# W061C.net
KiCad netlist of a schematic drawn in EAGLE
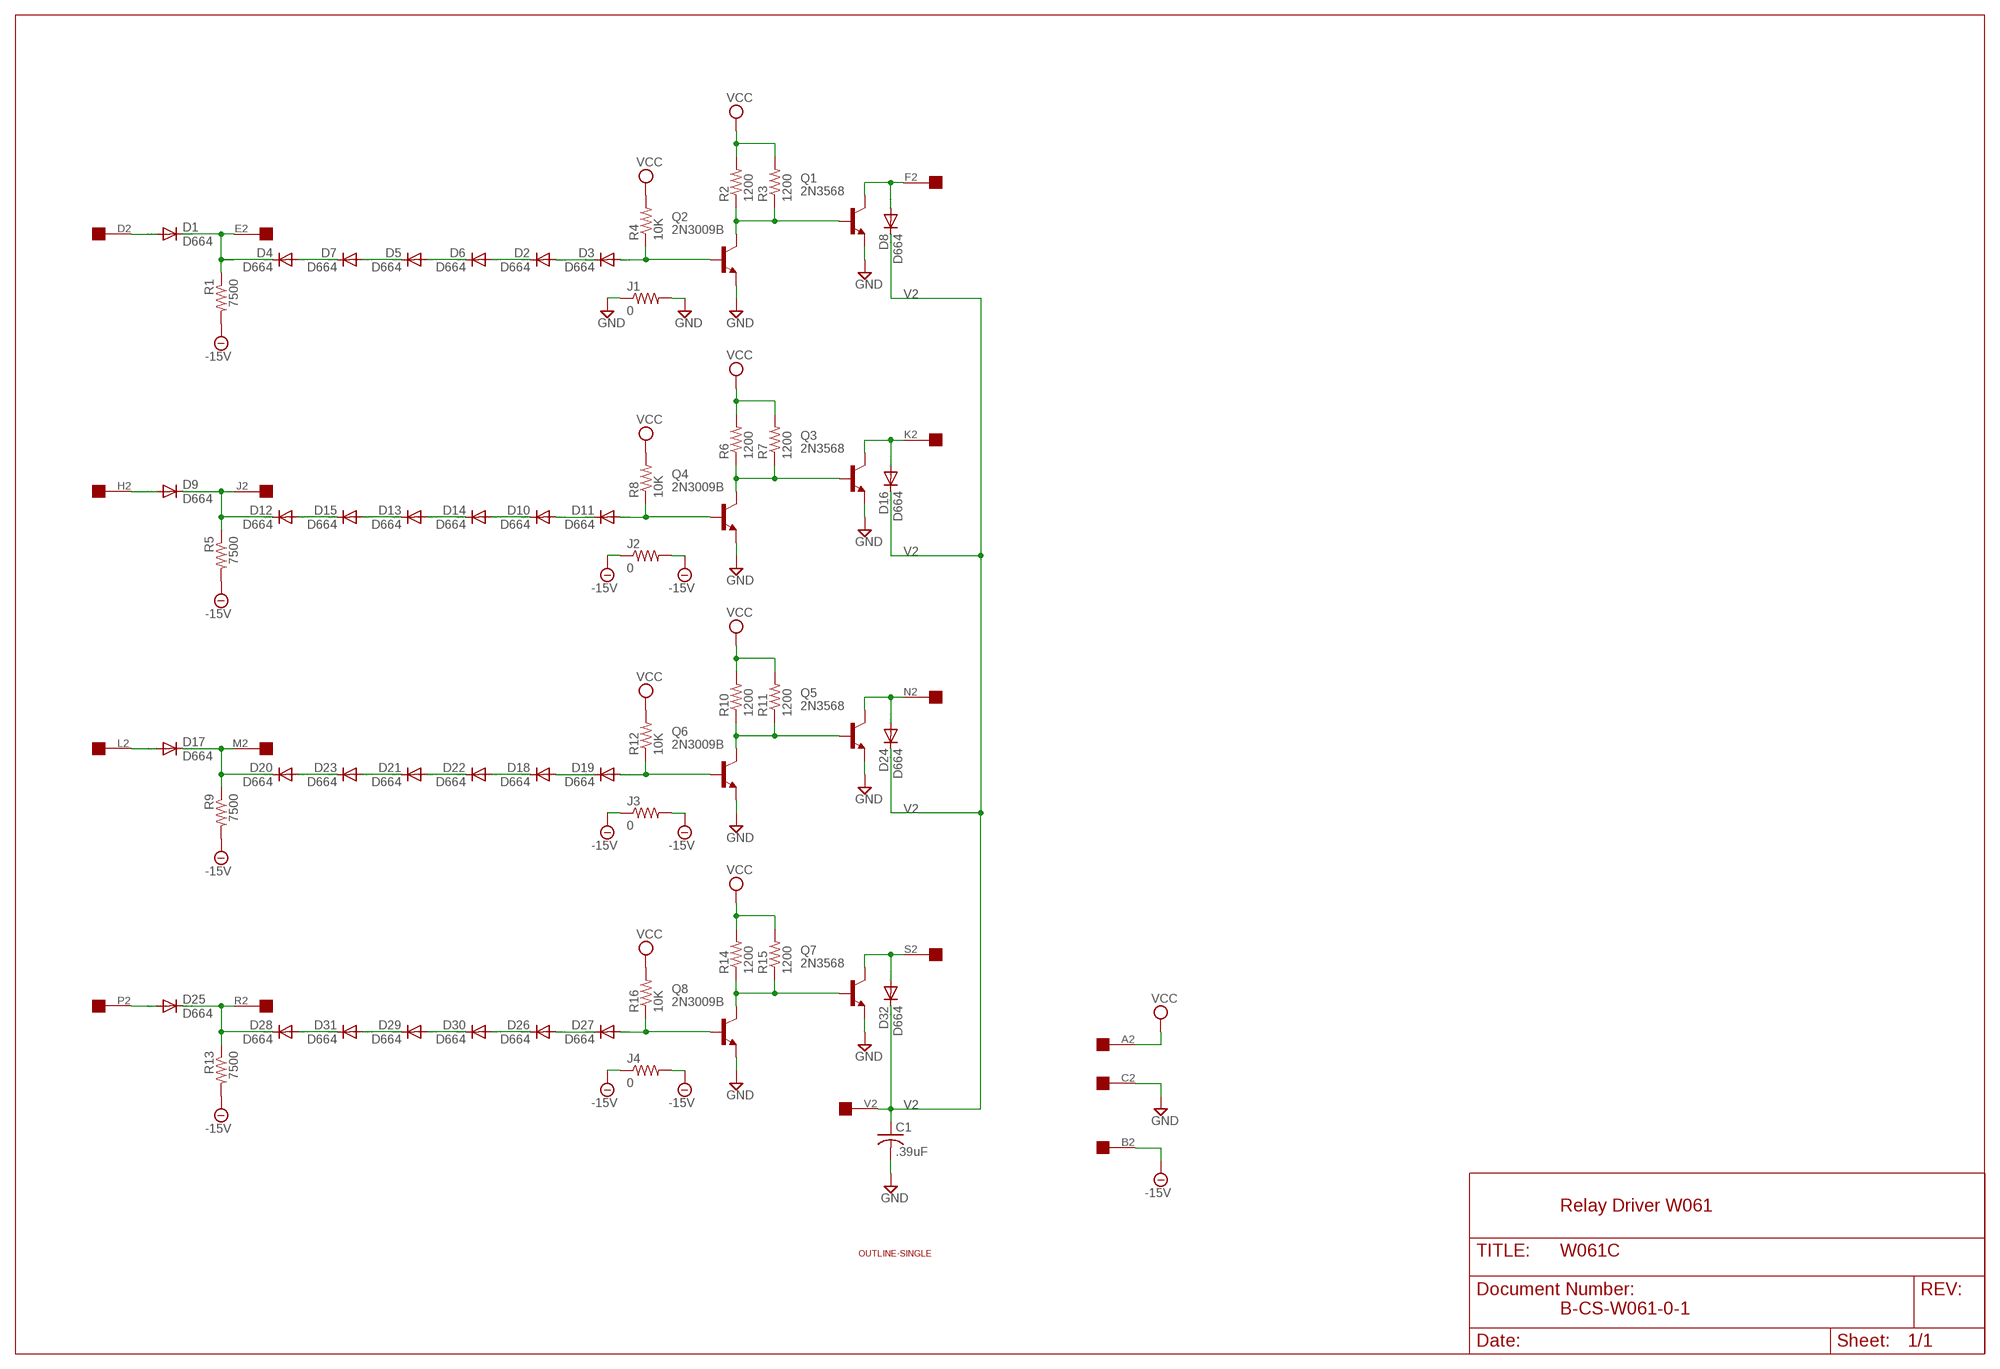
[diagram p0: schematic, sheet 1]

(export (version "E")
  (design (tool "Eeschema 10.0.6"))
  (components
    (comp (ref "C1")
      (value ".39uF")
      (footprint "eagle-import:C375-155X418")
      (libsource (lib "eagle-import") (part "C-US375-155X418"))
    )
    (comp (ref "D1")
      (value "D664")
      (footprint "eagle-import:DO35-10")
      (libsource (lib "eagle-import") (part "DIODE-DO35-10"))
    )
    (comp (ref "D2")
      (value "D664")
      (footprint "eagle-import:DO35-10")
      (libsource (lib "eagle-import") (part "DIODE-DO35-10"))
    )
    (comp (ref "D3")
      (value "D664")
      (footprint "eagle-import:DO35-10")
      (libsource (lib "eagle-import") (part "DIODE-DO35-10"))
    )
    (comp (ref "D4")
      (value "D664")
      (footprint "eagle-import:DO35-10")
      (libsource (lib "eagle-import") (part "DIODE-DO35-10"))
    )
    (comp (ref "D5")
      (value "D664")
      (footprint "eagle-import:DO35-10")
      (libsource (lib "eagle-import") (part "DIODE-DO35-10"))
    )
    (comp (ref "D6")
      (value "D664")
      (footprint "eagle-import:DO35-10")
      (libsource (lib "eagle-import") (part "DIODE-DO35-10"))
    )
    (comp (ref "D7")
      (value "D664")
      (footprint "eagle-import:DO35-10")
      (libsource (lib "eagle-import") (part "DIODE-DO35-10"))
    )
    (comp (ref "D8")
      (value "D664")
      (footprint "eagle-import:DO35-10")
      (libsource (lib "eagle-import") (part "DIODE-DO35-10"))
    )
    (comp (ref "D9")
      (value "D664")
      (footprint "eagle-import:DO35-10")
      (libsource (lib "eagle-import") (part "DIODE-DO35-10"))
    )
    (comp (ref "D10")
      (value "D664")
      (footprint "eagle-import:DO35-10")
      (libsource (lib "eagle-import") (part "DIODE-DO35-10"))
    )
    (comp (ref "D11")
      (value "D664")
      (footprint "eagle-import:DO35-10")
      (libsource (lib "eagle-import") (part "DIODE-DO35-10"))
    )
    (comp (ref "D12")
      (value "D664")
      (footprint "eagle-import:DO35-10")
      (libsource (lib "eagle-import") (part "DIODE-DO35-10"))
    )
    (comp (ref "D13")
      (value "D664")
      (footprint "eagle-import:DO35-10")
      (libsource (lib "eagle-import") (part "DIODE-DO35-10"))
    )
    (comp (ref "D14")
      (value "D664")
      (footprint "eagle-import:DO35-10")
      (libsource (lib "eagle-import") (part "DIODE-DO35-10"))
    )
    (comp (ref "D15")
      (value "D664")
      (footprint "eagle-import:DO35-10")
      (libsource (lib "eagle-import") (part "DIODE-DO35-10"))
    )
    (comp (ref "D16")
      (value "D664")
      (footprint "eagle-import:DO35-10")
      (libsource (lib "eagle-import") (part "DIODE-DO35-10"))
    )
    (comp (ref "D17")
      (value "D664")
      (footprint "eagle-import:DO35-10")
      (libsource (lib "eagle-import") (part "DIODE-DO35-10"))
    )
    (comp (ref "D18")
      (value "D664")
      (footprint "eagle-import:DO35-10")
      (libsource (lib "eagle-import") (part "DIODE-DO35-10"))
    )
    (comp (ref "D19")
      (value "D664")
      (footprint "eagle-import:DO35-10")
      (libsource (lib "eagle-import") (part "DIODE-DO35-10"))
    )
    (comp (ref "D20")
      (value "D664")
      (footprint "eagle-import:DO35-10")
      (libsource (lib "eagle-import") (part "DIODE-DO35-10"))
    )
    (comp (ref "D21")
      (value "D664")
      (footprint "eagle-import:DO35-10")
      (libsource (lib "eagle-import") (part "DIODE-DO35-10"))
    )
    (comp (ref "D22")
      (value "D664")
      (footprint "eagle-import:DO35-10")
      (libsource (lib "eagle-import") (part "DIODE-DO35-10"))
    )
    (comp (ref "D23")
      (value "D664")
      (footprint "eagle-import:DO35-10")
      (libsource (lib "eagle-import") (part "DIODE-DO35-10"))
    )
    (comp (ref "D24")
      (value "D664")
      (footprint "eagle-import:DO35-10")
      (libsource (lib "eagle-import") (part "DIODE-DO35-10"))
    )
    (comp (ref "D25")
      (value "D664")
      (footprint "eagle-import:DO35-10")
      (libsource (lib "eagle-import") (part "DIODE-DO35-10"))
    )
    (comp (ref "D26")
      (value "D664")
      (footprint "eagle-import:DO35-10")
      (libsource (lib "eagle-import") (part "DIODE-DO35-10"))
    )
    (comp (ref "D27")
      (value "D664")
      (footprint "eagle-import:DO35-10")
      (libsource (lib "eagle-import") (part "DIODE-DO35-10"))
    )
    (comp (ref "D28")
      (value "D664")
      (footprint "eagle-import:DO35-10")
      (libsource (lib "eagle-import") (part "DIODE-DO35-10"))
    )
    (comp (ref "D29")
      (value "D664")
      (footprint "eagle-import:DO35-10")
      (libsource (lib "eagle-import") (part "DIODE-DO35-10"))
    )
    (comp (ref "D30")
      (value "D664")
      (footprint "eagle-import:DO35-10")
      (libsource (lib "eagle-import") (part "DIODE-DO35-10"))
    )
    (comp (ref "D31")
      (value "D664")
      (footprint "eagle-import:DO35-10")
      (libsource (lib "eagle-import") (part "DIODE-DO35-10"))
    )
    (comp (ref "D32")
      (value "D664")
      (footprint "eagle-import:DO35-10")
      (libsource (lib "eagle-import") (part "DIODE-DO35-10"))
    )
    (comp (ref "J1")
      (value "0")
      (footprint "eagle-import:0207_10")
      (libsource (lib "eagle-import") (part "R-US_0207/10"))
    )
    (comp (ref "J2")
      (value "0")
      (footprint "eagle-import:0207_10")
      (libsource (lib "eagle-import") (part "R-US_0207/10"))
    )
    (comp (ref "J3")
      (value "0")
      (footprint "eagle-import:0207_10")
      (libsource (lib "eagle-import") (part "R-US_0207/10"))
    )
    (comp (ref "J4")
      (value "0")
      (footprint "eagle-import:0207_10")
      (libsource (lib "eagle-import") (part "R-US_0207/10"))
    )
    (comp (ref "Q1")
      (value "2N3568")
      (footprint "eagle-import:TO5")
      (libsource (lib "eagle-import") (part "-NPN-TO5"))
    )
    (comp (ref "Q2")
      (value "2N3009B")
      (footprint "eagle-import:TO5")
      (libsource (lib "eagle-import") (part "-NPN-TO5"))
    )
    (comp (ref "Q3")
      (value "2N3568")
      (footprint "eagle-import:TO5")
      (libsource (lib "eagle-import") (part "-NPN-TO5"))
    )
    (comp (ref "Q4")
      (value "2N3009B")
      (footprint "eagle-import:TO5")
      (libsource (lib "eagle-import") (part "-NPN-TO5"))
    )
    (comp (ref "Q5")
      (value "2N3568")
      (footprint "eagle-import:TO5")
      (libsource (lib "eagle-import") (part "-NPN-TO5"))
    )
    (comp (ref "Q6")
      (value "2N3009B")
      (footprint "eagle-import:TO5")
      (libsource (lib "eagle-import") (part "-NPN-TO5"))
    )
    (comp (ref "Q7")
      (value "2N3568")
      (footprint "eagle-import:TO5")
      (libsource (lib "eagle-import") (part "-NPN-TO5"))
    )
    (comp (ref "Q8")
      (value "2N3009B")
      (footprint "eagle-import:TO5")
      (libsource (lib "eagle-import") (part "-NPN-TO5"))
    )
    (comp (ref "R1")
      (value "7500")
      (footprint "eagle-import:0207_10")
      (libsource (lib "eagle-import") (part "R-US_0207/10"))
    )
    (comp (ref "R2")
      (value "1200")
      (footprint "eagle-import:0207_10")
      (libsource (lib "eagle-import") (part "R-US_0207/10"))
    )
    (comp (ref "R3")
      (value "1200")
      (footprint "eagle-import:0207_10")
      (libsource (lib "eagle-import") (part "R-US_0207/10"))
    )
    (comp (ref "R4")
      (value "10K")
      (footprint "eagle-import:0207_10")
      (libsource (lib "eagle-import") (part "R-US_0207/10"))
    )
    (comp (ref "R5")
      (value "7500")
      (footprint "eagle-import:0207_10")
      (libsource (lib "eagle-import") (part "R-US_0207/10"))
    )
    (comp (ref "R6")
      (value "1200")
      (footprint "eagle-import:0207_10")
      (libsource (lib "eagle-import") (part "R-US_0207/10"))
    )
    (comp (ref "R7")
      (value "1200")
      (footprint "eagle-import:0207_10")
      (libsource (lib "eagle-import") (part "R-US_0207/10"))
    )
    (comp (ref "R8")
      (value "10K")
      (footprint "eagle-import:0207_10")
      (libsource (lib "eagle-import") (part "R-US_0207/10"))
    )
    (comp (ref "R9")
      (value "7500")
      (footprint "eagle-import:0207_10")
      (libsource (lib "eagle-import") (part "R-US_0207/10"))
    )
    (comp (ref "R10")
      (value "1200")
      (footprint "eagle-import:0207_10")
      (libsource (lib "eagle-import") (part "R-US_0207/10"))
    )
    (comp (ref "R11")
      (value "1200")
      (footprint "eagle-import:0207_10")
      (libsource (lib "eagle-import") (part "R-US_0207/10"))
    )
    (comp (ref "R12")
      (value "10K")
      (footprint "eagle-import:0207_10")
      (libsource (lib "eagle-import") (part "R-US_0207/10"))
    )
    (comp (ref "R13")
      (value "7500")
      (footprint "eagle-import:0207_10")
      (libsource (lib "eagle-import") (part "R-US_0207/10"))
    )
    (comp (ref "R14")
      (value "1200")
      (footprint "eagle-import:0207_10")
      (libsource (lib "eagle-import") (part "R-US_0207/10"))
    )
    (comp (ref "R15")
      (value "1200")
      (footprint "eagle-import:0207_10")
      (libsource (lib "eagle-import") (part "R-US_0207/10"))
    )
    (comp (ref "R16")
      (value "10K")
      (footprint "eagle-import:0207_10")
      (libsource (lib "eagle-import") (part "R-US_0207/10"))
    )
    (comp (ref "U$1")
      (value "OUTLINE-SINGLE")
      (footprint "eagle-import:SINGLE")
      (libsource (lib "eagle-import") (part "OUTLINE-SINGLE"))
    )
    (comp (ref "U$2")
      (value "EDGE-1")
      (footprint "eagle-import:EDGE-CON1")
      (libsource (lib "eagle-import") (part "EDGE-1"))
    )
  )
  (nets
    (net (code "1") (name "-15V") (class "Default")
      (node (ref "J2") (pin "1") (pinfunction "1_1") (pintype "passive"))
      (node (ref "J2") (pin "2") (pinfunction "2_2") (pintype "passive"))
      (node (ref "J3") (pin "1") (pinfunction "1_1") (pintype "passive"))
      (node (ref "J3") (pin "2") (pinfunction "2_2") (pintype "passive"))
      (node (ref "J4") (pin "1") (pinfunction "1_1") (pintype "passive"))
      (node (ref "J4") (pin "2") (pinfunction "2_2") (pintype "passive"))
      (node (ref "R1") (pin "2") (pinfunction "2_2") (pintype "passive"))
      (node (ref "R13") (pin "2") (pinfunction "2_2") (pintype "passive"))
      (node (ref "R5") (pin "2") (pinfunction "2_2") (pintype "passive"))
      (node (ref "R9") (pin "2") (pinfunction "2_2") (pintype "passive"))
      (node (ref "U$2") (pin "B2") (pinfunction "1_B2") (pintype "bidirectional"))
    )
    (net (code "2") (name "/V2") (class "Default")
      (node (ref "C1") (pin "1") (pinfunction "1_1") (pintype "passive"))
      (node (ref "D16") (pin "C") (pinfunction "C_C") (pintype "passive"))
      (node (ref "D24") (pin "C") (pinfunction "C_C") (pintype "passive"))
      (node (ref "D32") (pin "C") (pinfunction "C_C") (pintype "passive"))
      (node (ref "D8") (pin "C") (pinfunction "C_C") (pintype "passive"))
      (node (ref "U$2") (pin "V2") (pinfunction "1_V2") (pintype "bidirectional"))
    )
    (net (code "3") (name "GND") (class "Default")
      (node (ref "C1") (pin "2") (pinfunction "2_2") (pintype "passive"))
      (node (ref "J1") (pin "1") (pinfunction "1_1") (pintype "passive"))
      (node (ref "J1") (pin "2") (pinfunction "2_2") (pintype "passive"))
      (node (ref "Q1") (pin "1") (pinfunction "E_1") (pintype "passive"))
      (node (ref "Q2") (pin "1") (pinfunction "E_1") (pintype "passive"))
      (node (ref "Q3") (pin "1") (pinfunction "E_1") (pintype "passive"))
      (node (ref "Q4") (pin "1") (pinfunction "E_1") (pintype "passive"))
      (node (ref "Q5") (pin "1") (pinfunction "E_1") (pintype "passive"))
      (node (ref "Q6") (pin "1") (pinfunction "E_1") (pintype "passive"))
      (node (ref "Q7") (pin "1") (pinfunction "E_1") (pintype "passive"))
      (node (ref "Q8") (pin "1") (pinfunction "E_1") (pintype "passive"))
      (node (ref "U$2") (pin "C2") (pinfunction "1_C2") (pintype "bidirectional"))
    )
    (net (code "4") (name "Net-(D2-PadA)") (class "Default")
      (node (ref "D2") (pin "A") (pinfunction "A_A") (pintype "passive"))
      (node (ref "D3") (pin "C") (pinfunction "C_C") (pintype "passive"))
    )
    (net (code "5") (name "Net-(D2-PadC)") (class "Default")
      (node (ref "D2") (pin "C") (pinfunction "C_C") (pintype "passive"))
      (node (ref "D6") (pin "A") (pinfunction "A_A") (pintype "passive"))
    )
    (net (code "6") (name "Net-(D4-PadA)") (class "Default")
      (node (ref "D4") (pin "A") (pinfunction "A_A") (pintype "passive"))
      (node (ref "D7") (pin "C") (pinfunction "C_C") (pintype "passive"))
    )
    (net (code "7") (name "Net-(D5-PadA)") (class "Default")
      (node (ref "D5") (pin "A") (pinfunction "A_A") (pintype "passive"))
      (node (ref "D6") (pin "C") (pinfunction "C_C") (pintype "passive"))
    )
    (net (code "8") (name "Net-(D5-PadC)") (class "Default")
      (node (ref "D5") (pin "C") (pinfunction "C_C") (pintype "passive"))
      (node (ref "D7") (pin "A") (pinfunction "A_A") (pintype "passive"))
    )
    (net (code "9") (name "Net-(D10-PadA)") (class "Default")
      (node (ref "D10") (pin "A") (pinfunction "A_A") (pintype "passive"))
      (node (ref "D11") (pin "C") (pinfunction "C_C") (pintype "passive"))
    )
    (net (code "10") (name "Net-(D10-PadC)") (class "Default")
      (node (ref "D10") (pin "C") (pinfunction "C_C") (pintype "passive"))
      (node (ref "D14") (pin "A") (pinfunction "A_A") (pintype "passive"))
    )
    (net (code "11") (name "Net-(D12-PadA)") (class "Default")
      (node (ref "D12") (pin "A") (pinfunction "A_A") (pintype "passive"))
      (node (ref "D15") (pin "C") (pinfunction "C_C") (pintype "passive"))
    )
    (net (code "12") (name "Net-(D13-PadA)") (class "Default")
      (node (ref "D13") (pin "A") (pinfunction "A_A") (pintype "passive"))
      (node (ref "D14") (pin "C") (pinfunction "C_C") (pintype "passive"))
    )
    (net (code "13") (name "Net-(D13-PadC)") (class "Default")
      (node (ref "D13") (pin "C") (pinfunction "C_C") (pintype "passive"))
      (node (ref "D15") (pin "A") (pinfunction "A_A") (pintype "passive"))
    )
    (net (code "14") (name "Net-(D18-PadA)") (class "Default")
      (node (ref "D18") (pin "A") (pinfunction "A_A") (pintype "passive"))
      (node (ref "D19") (pin "C") (pinfunction "C_C") (pintype "passive"))
    )
    (net (code "15") (name "Net-(D18-PadC)") (class "Default")
      (node (ref "D18") (pin "C") (pinfunction "C_C") (pintype "passive"))
      (node (ref "D22") (pin "A") (pinfunction "A_A") (pintype "passive"))
    )
    (net (code "16") (name "Net-(D20-PadA)") (class "Default")
      (node (ref "D20") (pin "A") (pinfunction "A_A") (pintype "passive"))
      (node (ref "D23") (pin "C") (pinfunction "C_C") (pintype "passive"))
    )
    (net (code "17") (name "Net-(D21-PadA)") (class "Default")
      (node (ref "D21") (pin "A") (pinfunction "A_A") (pintype "passive"))
      (node (ref "D22") (pin "C") (pinfunction "C_C") (pintype "passive"))
    )
    (net (code "18") (name "Net-(D21-PadC)") (class "Default")
      (node (ref "D21") (pin "C") (pinfunction "C_C") (pintype "passive"))
      (node (ref "D23") (pin "A") (pinfunction "A_A") (pintype "passive"))
    )
    (net (code "19") (name "Net-(D26-PadA)") (class "Default")
      (node (ref "D26") (pin "A") (pinfunction "A_A") (pintype "passive"))
      (node (ref "D27") (pin "C") (pinfunction "C_C") (pintype "passive"))
    )
    (net (code "20") (name "Net-(D26-PadC)") (class "Default")
      (node (ref "D26") (pin "C") (pinfunction "C_C") (pintype "passive"))
      (node (ref "D30") (pin "A") (pinfunction "A_A") (pintype "passive"))
    )
    (net (code "21") (name "Net-(D28-PadA)") (class "Default")
      (node (ref "D28") (pin "A") (pinfunction "A_A") (pintype "passive"))
      (node (ref "D31") (pin "C") (pinfunction "C_C") (pintype "passive"))
    )
    (net (code "22") (name "Net-(D29-PadA)") (class "Default")
      (node (ref "D29") (pin "A") (pinfunction "A_A") (pintype "passive"))
      (node (ref "D30") (pin "C") (pinfunction "C_C") (pintype "passive"))
    )
    (net (code "23") (name "Net-(D29-PadC)") (class "Default")
      (node (ref "D29") (pin "C") (pinfunction "C_C") (pintype "passive"))
      (node (ref "D31") (pin "A") (pinfunction "A_A") (pintype "passive"))
    )
    (net (code "24") (name "Net-(Q1-B)") (class "Default")
      (node (ref "Q1") (pin "2") (pinfunction "B_2") (pintype "passive"))
      (node (ref "Q2") (pin "3") (pinfunction "C_3") (pintype "passive"))
      (node (ref "R2") (pin "1") (pinfunction "1_1") (pintype "passive"))
      (node (ref "R3") (pin "1") (pinfunction "1_1") (pintype "passive"))
    )
    (net (code "25") (name "Net-(Q1-C)") (class "Default")
      (node (ref "D8") (pin "A") (pinfunction "A_A") (pintype "passive"))
      (node (ref "Q1") (pin "3") (pinfunction "C_3") (pintype "passive"))
      (node (ref "U$2") (pin "F2") (pinfunction "1_F2") (pintype "bidirectional"))
    )
    (net (code "26") (name "Net-(Q2-B)") (class "Default")
      (node (ref "D3") (pin "A") (pinfunction "A_A") (pintype "passive"))
      (node (ref "Q2") (pin "2") (pinfunction "B_2") (pintype "passive"))
      (node (ref "R4") (pin "1") (pinfunction "1_1") (pintype "passive"))
    )
    (net (code "27") (name "Net-(Q3-B)") (class "Default")
      (node (ref "Q3") (pin "2") (pinfunction "B_2") (pintype "passive"))
      (node (ref "Q4") (pin "3") (pinfunction "C_3") (pintype "passive"))
      (node (ref "R6") (pin "1") (pinfunction "1_1") (pintype "passive"))
      (node (ref "R7") (pin "1") (pinfunction "1_1") (pintype "passive"))
    )
    (net (code "28") (name "Net-(Q3-C)") (class "Default")
      (node (ref "D16") (pin "A") (pinfunction "A_A") (pintype "passive"))
      (node (ref "Q3") (pin "3") (pinfunction "C_3") (pintype "passive"))
      (node (ref "U$2") (pin "K2") (pinfunction "1_K2") (pintype "bidirectional"))
    )
    (net (code "29") (name "Net-(Q4-B)") (class "Default")
      (node (ref "D11") (pin "A") (pinfunction "A_A") (pintype "passive"))
      (node (ref "Q4") (pin "2") (pinfunction "B_2") (pintype "passive"))
      (node (ref "R8") (pin "1") (pinfunction "1_1") (pintype "passive"))
    )
    (net (code "30") (name "Net-(Q5-B)") (class "Default")
      (node (ref "Q5") (pin "2") (pinfunction "B_2") (pintype "passive"))
      (node (ref "Q6") (pin "3") (pinfunction "C_3") (pintype "passive"))
      (node (ref "R10") (pin "1") (pinfunction "1_1") (pintype "passive"))
      (node (ref "R11") (pin "1") (pinfunction "1_1") (pintype "passive"))
    )
    (net (code "31") (name "Net-(Q5-C)") (class "Default")
      (node (ref "D24") (pin "A") (pinfunction "A_A") (pintype "passive"))
      (node (ref "Q5") (pin "3") (pinfunction "C_3") (pintype "passive"))
      (node (ref "U$2") (pin "N2") (pinfunction "1_N2") (pintype "bidirectional"))
    )
    (net (code "32") (name "Net-(Q6-B)") (class "Default")
      (node (ref "D19") (pin "A") (pinfunction "A_A") (pintype "passive"))
      (node (ref "Q6") (pin "2") (pinfunction "B_2") (pintype "passive"))
      (node (ref "R12") (pin "1") (pinfunction "1_1") (pintype "passive"))
    )
    (net (code "33") (name "Net-(Q7-B)") (class "Default")
      (node (ref "Q7") (pin "2") (pinfunction "B_2") (pintype "passive"))
      (node (ref "Q8") (pin "3") (pinfunction "C_3") (pintype "passive"))
      (node (ref "R14") (pin "1") (pinfunction "1_1") (pintype "passive"))
      (node (ref "R15") (pin "1") (pinfunction "1_1") (pintype "passive"))
    )
    (net (code "34") (name "Net-(Q7-C)") (class "Default")
      (node (ref "D32") (pin "A") (pinfunction "A_A") (pintype "passive"))
      (node (ref "Q7") (pin "3") (pinfunction "C_3") (pintype "passive"))
      (node (ref "U$2") (pin "S2") (pinfunction "1_S2") (pintype "bidirectional"))
    )
    (net (code "35") (name "Net-(Q8-B)") (class "Default")
      (node (ref "D27") (pin "A") (pinfunction "A_A") (pintype "passive"))
      (node (ref "Q8") (pin "2") (pinfunction "B_2") (pintype "passive"))
      (node (ref "R16") (pin "1") (pinfunction "1_1") (pintype "passive"))
    )
    (net (code "36") (name "Net-(U$2D-1)") (class "Default")
      (node (ref "D1") (pin "A") (pinfunction "A_A") (pintype "passive"))
      (node (ref "U$2") (pin "D2") (pinfunction "1_D2") (pintype "bidirectional"))
    )
    (net (code "37") (name "Net-(U$2E-1)") (class "Default")
      (node (ref "D1") (pin "C") (pinfunction "C_C") (pintype "passive"))
      (node (ref "D4") (pin "C") (pinfunction "C_C") (pintype "passive"))
      (node (ref "R1") (pin "1") (pinfunction "1_1") (pintype "passive"))
      (node (ref "U$2") (pin "E2") (pinfunction "1_E2") (pintype "bidirectional"))
    )
    (net (code "38") (name "Net-(U$2G-1)") (class "Default")
      (node (ref "D9") (pin "A") (pinfunction "A_A") (pintype "passive"))
      (node (ref "U$2") (pin "H2") (pinfunction "1_H2") (pintype "bidirectional"))
    )
    (net (code "39") (name "Net-(U$2H-1)") (class "Default")
      (node (ref "D12") (pin "C") (pinfunction "C_C") (pintype "passive"))
      (node (ref "D9") (pin "C") (pinfunction "C_C") (pintype "passive"))
      (node (ref "R5") (pin "1") (pinfunction "1_1") (pintype "passive"))
      (node (ref "U$2") (pin "J2") (pinfunction "1_J2") (pintype "bidirectional"))
    )
    (net (code "40") (name "Net-(U$2J-1)") (class "Default")
      (node (ref "D17") (pin "A") (pinfunction "A_A") (pintype "passive"))
      (node (ref "U$2") (pin "L2") (pinfunction "1_L2") (pintype "bidirectional"))
    )
    (net (code "41") (name "Net-(U$2K-1)") (class "Default")
      (node (ref "D17") (pin "C") (pinfunction "C_C") (pintype "passive"))
      (node (ref "D20") (pin "C") (pinfunction "C_C") (pintype "passive"))
      (node (ref "R9") (pin "1") (pinfunction "1_1") (pintype "passive"))
      (node (ref "U$2") (pin "M2") (pinfunction "1_M2") (pintype "bidirectional"))
    )
    (net (code "42") (name "Net-(U$2M-1)") (class "Default")
      (node (ref "D25") (pin "A") (pinfunction "A_A") (pintype "passive"))
      (node (ref "U$2") (pin "P2") (pinfunction "1_P2") (pintype "bidirectional"))
    )
    (net (code "43") (name "Net-(U$2N-1)") (class "Default")
      (node (ref "D25") (pin "C") (pinfunction "C_C") (pintype "passive"))
      (node (ref "D28") (pin "C") (pinfunction "C_C") (pintype "passive"))
      (node (ref "R13") (pin "1") (pinfunction "1_1") (pintype "passive"))
      (node (ref "U$2") (pin "R2") (pinfunction "1_R2") (pintype "bidirectional"))
    )
    (net (code "44") (name "VCC") (class "Default")
      (node (ref "R10") (pin "2") (pinfunction "2_2") (pintype "passive"))
      (node (ref "R11") (pin "2") (pinfunction "2_2") (pintype "passive"))
      (node (ref "R12") (pin "2") (pinfunction "2_2") (pintype "passive"))
      (node (ref "R14") (pin "2") (pinfunction "2_2") (pintype "passive"))
      (node (ref "R15") (pin "2") (pinfunction "2_2") (pintype "passive"))
      (node (ref "R16") (pin "2") (pinfunction "2_2") (pintype "passive"))
      (node (ref "R2") (pin "2") (pinfunction "2_2") (pintype "passive"))
      (node (ref "R3") (pin "2") (pinfunction "2_2") (pintype "passive"))
      (node (ref "R4") (pin "2") (pinfunction "2_2") (pintype "passive"))
      (node (ref "R6") (pin "2") (pinfunction "2_2") (pintype "passive"))
      (node (ref "R7") (pin "2") (pinfunction "2_2") (pintype "passive"))
      (node (ref "R8") (pin "2") (pinfunction "2_2") (pintype "passive"))
      (node (ref "U$2") (pin "A2") (pinfunction "1_A2") (pintype "bidirectional"))
    )
  )
)
